# axiom_beta_interface_dummy_v0_7_eca36251.net
KiCad netlist of a schematic drawn in EAGLE
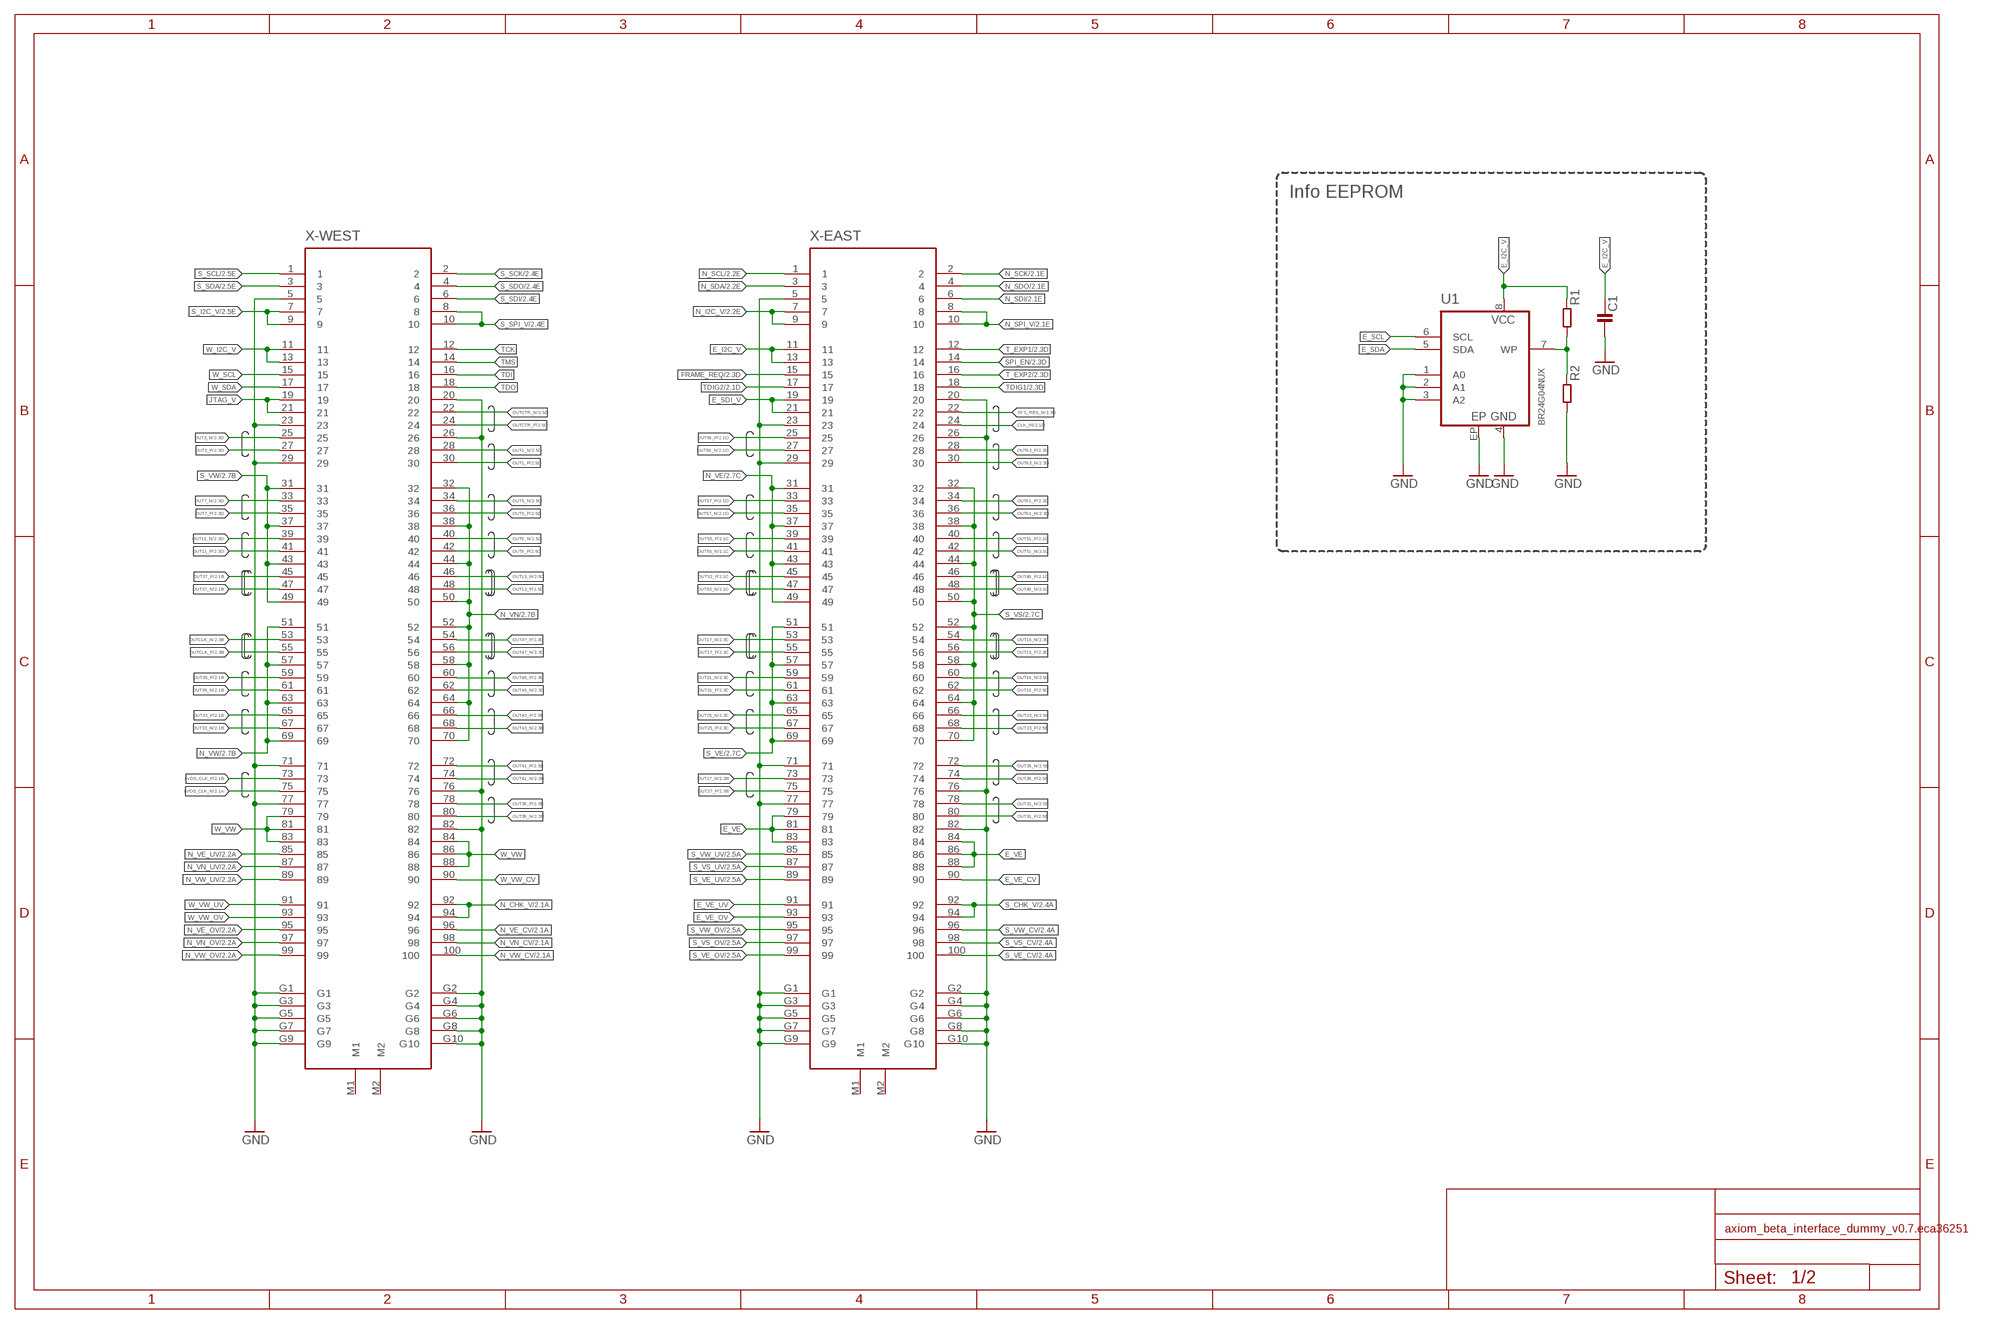
[diagram p0: schematic, sheet 1]
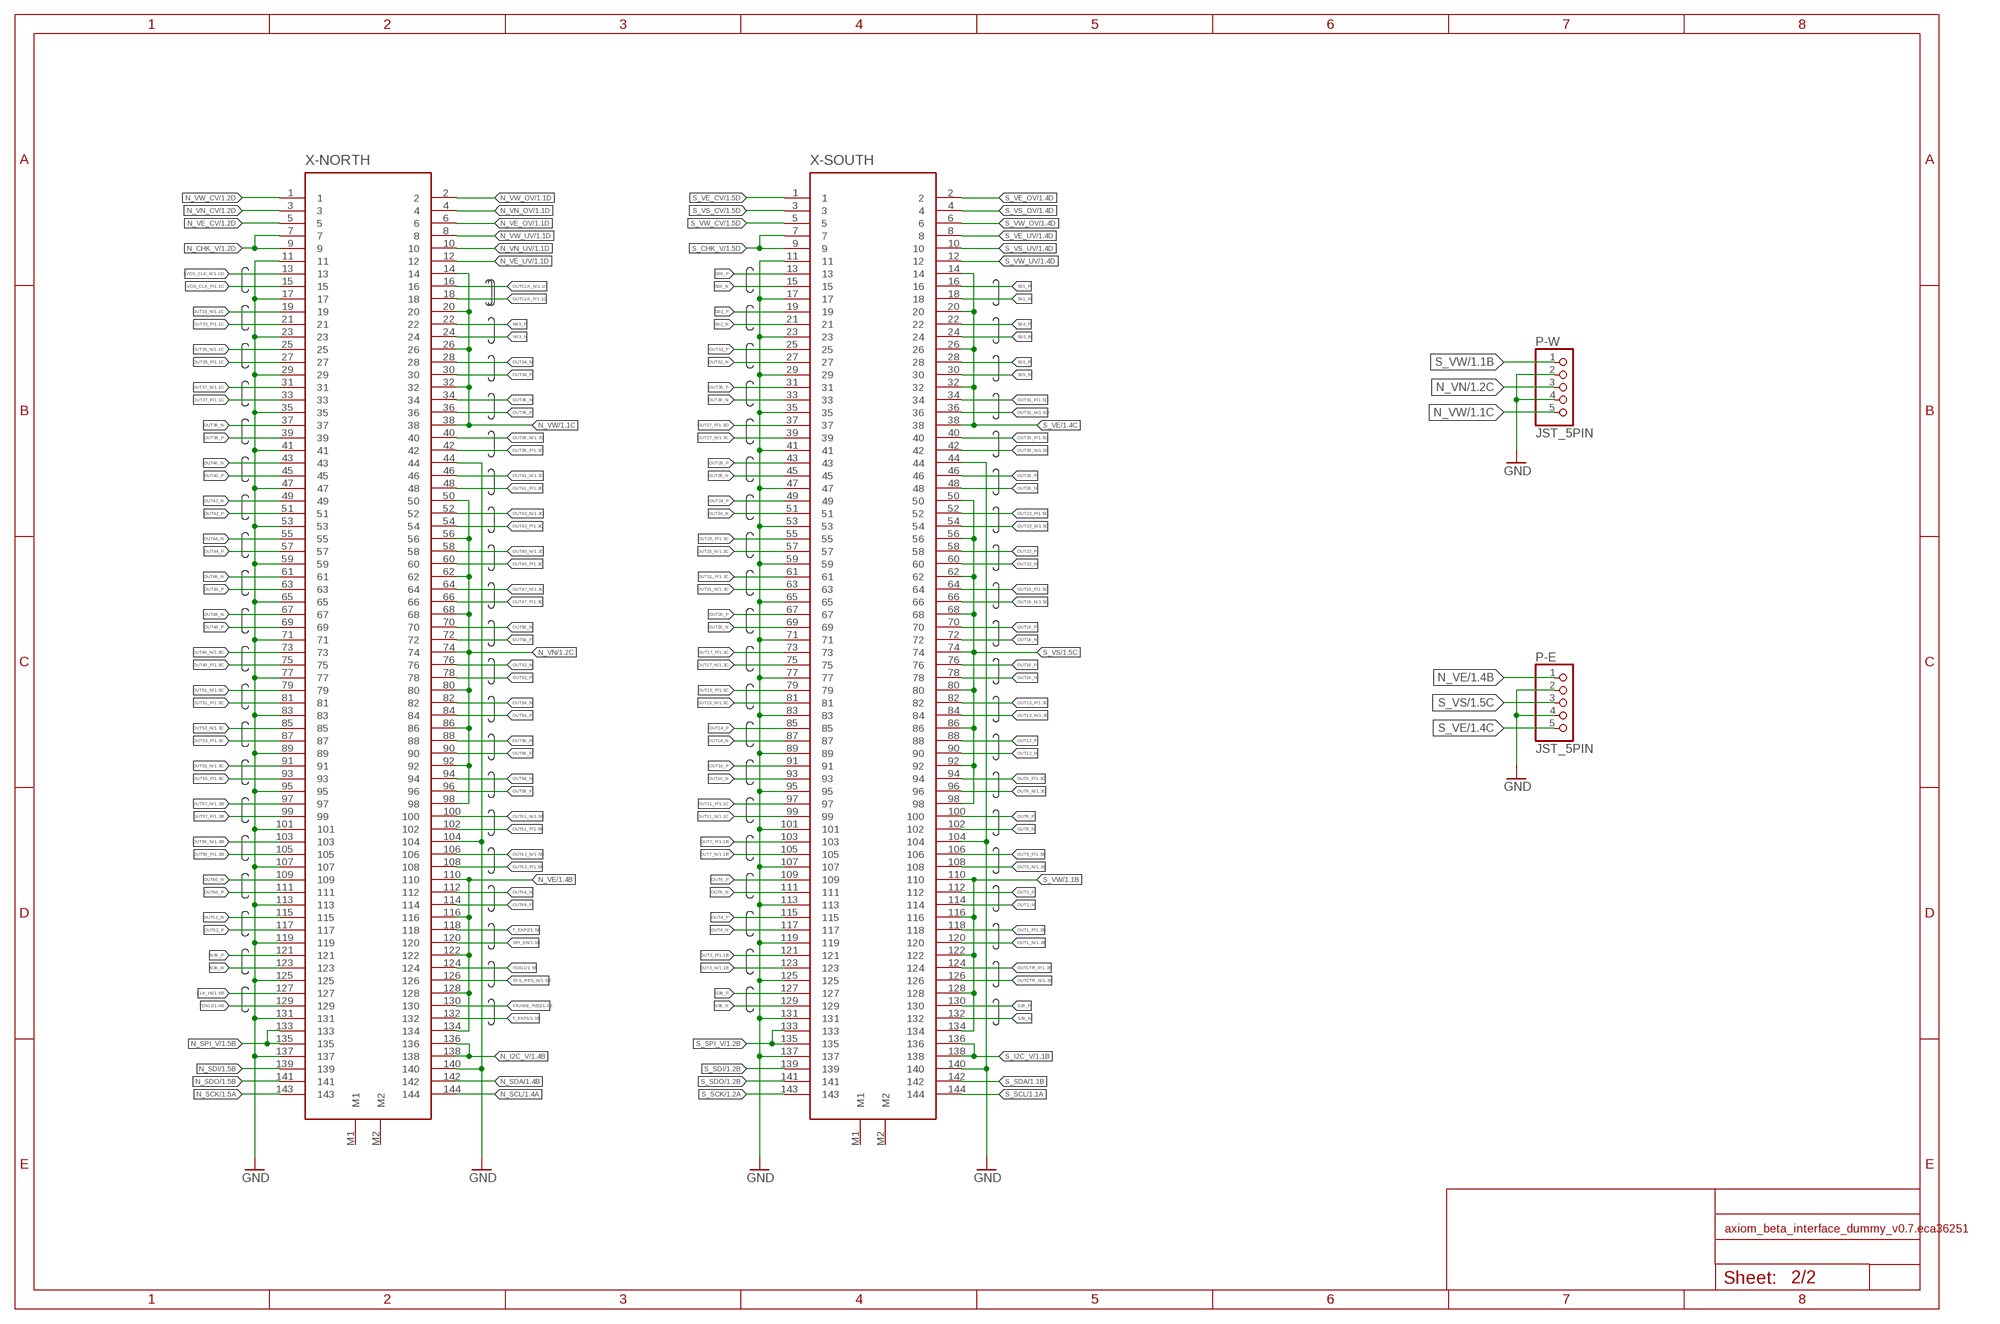
[diagram p1: schematic, sheet 2]

(export (version "E")
  (design (tool "Eeschema 10.0.6"))
  (components
    (comp (ref "P-E")
      (value "JST_5PIN")
      (footprint "eagle-import:JST-PH-5-SMT-RA")
      (libsource (lib "eagle-import") (part "JST_5PIN"))
    )
    (comp (ref "P-W")
      (value "JST_5PIN")
      (footprint "eagle-import:JST-PH-5-SMT-RA")
      (libsource (lib "eagle-import") (part "JST_5PIN"))
    )
    (comp (ref "X-NORTH")
      (value "FX10-144S")
      (footprint "eagle-import:FX10A-144S")
      (libsource (lib "eagle-import") (part "FX10-144S"))
    )
    (comp (ref "X-SOUTH")
      (value "FX10-144S")
      (footprint "eagle-import:FX10A-144S")
      (libsource (lib "eagle-import") (part "FX10-144S"))
    )
    (comp (ref "C1")
      (value "C0402-B")
      (footprint "eagle-import:0402-B")
      (libsource (lib "eagle-import") (part "C0402-B"))
    )
    (comp (ref "R1")
      (value "R0402-B")
      (footprint "eagle-import:0402-B")
      (libsource (lib "eagle-import") (part "R0402-B"))
    )
    (comp (ref "R2")
      (value "R0402-B")
      (footprint "eagle-import:0402-B")
      (libsource (lib "eagle-import") (part "R0402-B"))
    )
    (comp (ref "U1")
      (value "BR24G04NUX")
      (footprint "eagle-import:DFN200X300X100-9N")
      (libsource (lib "eagle-import") (part "BR24G04NUX"))
    )
    (comp (ref "X-EAST")
      (value "FX10-100/10P")
      (footprint "eagle-import:FX10A-100P_10")
      (libsource (lib "eagle-import") (part "FX10-100/10P"))
    )
    (comp (ref "X-WEST")
      (value "FX10-100/10P")
      (footprint "eagle-import:FX10A-100P_10")
      (libsource (lib "eagle-import") (part "FX10-100/10P"))
    )
  )
  (nets
    (net (code "1") (name "CLK_IN") (class "Default")
      (node (ref "X-EAST") (pin "24") (pinfunction "24_24") (pintype "bidirectional"))
      (node (ref "X-NORTH") (pin "127") (pinfunction "127_127") (pintype "bidirectional"))
    )
    (net (code "2") (name "E_I2C_V") (class "Default")
      (node (ref "C1") (pin "1") (pinfunction "1_1") (pintype "passive"))
      (node (ref "R1") (pin "1") (pinfunction "1_1") (pintype "passive"))
      (node (ref "U1") (pin "8") (pinfunction "VCC_8") (pintype "power_in"))
      (node (ref "X-EAST") (pin "11") (pinfunction "11_11") (pintype "bidirectional"))
      (node (ref "X-EAST") (pin "13") (pinfunction "13_13") (pintype "bidirectional"))
    )
    (net (code "3") (name "E_SCL") (class "Default")
      (node (ref "U1") (pin "6") (pinfunction "SCL_6") (pintype "input"))
    )
    (net (code "4") (name "E_SDA") (class "Default")
      (node (ref "U1") (pin "5") (pinfunction "SDA_5") (pintype "bidirectional"))
    )
    (net (code "5") (name "E_SDI_V") (class "Default")
      (node (ref "X-EAST") (pin "19") (pinfunction "19_19") (pintype "bidirectional"))
      (node (ref "X-EAST") (pin "21") (pinfunction "21_21") (pintype "bidirectional"))
    )
    (net (code "6") (name "E_VE") (class "Default")
      (node (ref "X-EAST") (pin "79") (pinfunction "79_79") (pintype "bidirectional"))
      (node (ref "X-EAST") (pin "81") (pinfunction "81_81") (pintype "bidirectional"))
      (node (ref "X-EAST") (pin "83") (pinfunction "83_83") (pintype "bidirectional"))
      (node (ref "X-EAST") (pin "84") (pinfunction "84_84") (pintype "bidirectional"))
      (node (ref "X-EAST") (pin "86") (pinfunction "86_86") (pintype "bidirectional"))
      (node (ref "X-EAST") (pin "88") (pinfunction "88_88") (pintype "bidirectional"))
    )
    (net (code "7") (name "E_VE_CV") (class "Default")
      (node (ref "X-EAST") (pin "90") (pinfunction "90_90") (pintype "bidirectional"))
    )
    (net (code "8") (name "E_VE_OV") (class "Default")
      (node (ref "X-EAST") (pin "93") (pinfunction "93_93") (pintype "bidirectional"))
    )
    (net (code "9") (name "E_VE_UV") (class "Default")
      (node (ref "X-EAST") (pin "91") (pinfunction "91_91") (pintype "bidirectional"))
    )
    (net (code "10") (name "FRAME_REQ") (class "Default")
      (node (ref "X-EAST") (pin "15") (pinfunction "15_15") (pintype "bidirectional"))
      (node (ref "X-NORTH") (pin "130") (pinfunction "130_130") (pintype "bidirectional"))
    )
    (net (code "11") (name "GND") (class "Default")
      (node (ref "C1") (pin "2") (pinfunction "2_2") (pintype "passive"))
      (node (ref "P-E") (pin "2") (pinfunction "2_2") (pintype "passive"))
      (node (ref "P-E") (pin "4") (pinfunction "4_4") (pintype "passive"))
      (node (ref "P-W") (pin "2") (pinfunction "2_2") (pintype "passive"))
      (node (ref "P-W") (pin "4") (pinfunction "4_4") (pintype "passive"))
      (node (ref "R2") (pin "2") (pinfunction "2_2") (pintype "passive"))
      (node (ref "U1") (pin "1") (pinfunction "A0_1") (pintype "input"))
      (node (ref "U1") (pin "2") (pinfunction "A1_2") (pintype "input"))
      (node (ref "U1") (pin "3") (pinfunction "A2_3") (pintype "input"))
      (node (ref "U1") (pin "4") (pinfunction "GND_4") (pintype "passive"))
      (node (ref "U1") (pin "EP") (pinfunction "EP_EP") (pintype "passive"))
      (node (ref "X-EAST") (pin "20") (pinfunction "20_20") (pintype "bidirectional"))
      (node (ref "X-EAST") (pin "23") (pinfunction "23_23") (pintype "bidirectional"))
      (node (ref "X-EAST") (pin "26") (pinfunction "26_26") (pintype "bidirectional"))
      (node (ref "X-EAST") (pin "29") (pinfunction "29_29") (pintype "bidirectional"))
      (node (ref "X-EAST") (pin "5") (pinfunction "5_5") (pintype "bidirectional"))
      (node (ref "X-EAST") (pin "71") (pinfunction "71_71") (pintype "bidirectional"))
      (node (ref "X-EAST") (pin "76") (pinfunction "76_76") (pintype "bidirectional"))
      (node (ref "X-EAST") (pin "77") (pinfunction "77_77") (pintype "bidirectional"))
      (node (ref "X-EAST") (pin "82") (pinfunction "82_82") (pintype "bidirectional"))
      (node (ref "X-EAST") (pin "G1") (pinfunction "G1_G1") (pintype "bidirectional"))
      (node (ref "X-EAST") (pin "G10") (pinfunction "G10_G10") (pintype "bidirectional"))
      (node (ref "X-EAST") (pin "G2") (pinfunction "G2_G2") (pintype "bidirectional"))
      (node (ref "X-EAST") (pin "G3") (pinfunction "G3_G3") (pintype "bidirectional"))
      (node (ref "X-EAST") (pin "G4") (pinfunction "G4_G4") (pintype "bidirectional"))
      (node (ref "X-EAST") (pin "G5") (pinfunction "G5_G5") (pintype "bidirectional"))
      (node (ref "X-EAST") (pin "G6") (pinfunction "G6_G6") (pintype "bidirectional"))
      (node (ref "X-EAST") (pin "G7") (pinfunction "G7_G7") (pintype "bidirectional"))
      (node (ref "X-EAST") (pin "G8") (pinfunction "G8_G8") (pintype "bidirectional"))
      (node (ref "X-EAST") (pin "G9") (pinfunction "G9_G9") (pintype "bidirectional"))
      (node (ref "X-NORTH") (pin "101") (pinfunction "101_101") (pintype "bidirectional"))
      (node (ref "X-NORTH") (pin "104") (pinfunction "104_104") (pintype "bidirectional"))
      (node (ref "X-NORTH") (pin "107") (pinfunction "107_107") (pintype "bidirectional"))
      (node (ref "X-NORTH") (pin "11") (pinfunction "11_11") (pintype "bidirectional"))
      (node (ref "X-NORTH") (pin "113") (pinfunction "113_113") (pintype "bidirectional"))
      (node (ref "X-NORTH") (pin "119") (pinfunction "119_119") (pintype "bidirectional"))
      (node (ref "X-NORTH") (pin "125") (pinfunction "125_125") (pintype "bidirectional"))
      (node (ref "X-NORTH") (pin "131") (pinfunction "131_131") (pintype "bidirectional"))
      (node (ref "X-NORTH") (pin "137") (pinfunction "137_137") (pintype "bidirectional"))
      (node (ref "X-NORTH") (pin "140") (pinfunction "140_140") (pintype "bidirectional"))
      (node (ref "X-NORTH") (pin "17") (pinfunction "17_17") (pintype "bidirectional"))
      (node (ref "X-NORTH") (pin "23") (pinfunction "23_23") (pintype "bidirectional"))
      (node (ref "X-NORTH") (pin "29") (pinfunction "29_29") (pintype "bidirectional"))
      (node (ref "X-NORTH") (pin "35") (pinfunction "35_35") (pintype "bidirectional"))
      (node (ref "X-NORTH") (pin "41") (pinfunction "41_41") (pintype "bidirectional"))
      (node (ref "X-NORTH") (pin "44") (pinfunction "44_44") (pintype "bidirectional"))
      (node (ref "X-NORTH") (pin "47") (pinfunction "47_47") (pintype "bidirectional"))
      (node (ref "X-NORTH") (pin "53") (pinfunction "53_53") (pintype "bidirectional"))
      (node (ref "X-NORTH") (pin "59") (pinfunction "59_59") (pintype "bidirectional"))
      (node (ref "X-NORTH") (pin "65") (pinfunction "65_65") (pintype "bidirectional"))
      (node (ref "X-NORTH") (pin "71") (pinfunction "71_71") (pintype "bidirectional"))
      (node (ref "X-NORTH") (pin "77") (pinfunction "77_77") (pintype "bidirectional"))
      (node (ref "X-NORTH") (pin "83") (pinfunction "83_83") (pintype "bidirectional"))
      (node (ref "X-NORTH") (pin "89") (pinfunction "89_89") (pintype "bidirectional"))
      (node (ref "X-NORTH") (pin "95") (pinfunction "95_95") (pintype "bidirectional"))
      (node (ref "X-SOUTH") (pin "101") (pinfunction "101_101") (pintype "bidirectional"))
      (node (ref "X-SOUTH") (pin "104") (pinfunction "104_104") (pintype "bidirectional"))
      (node (ref "X-SOUTH") (pin "107") (pinfunction "107_107") (pintype "bidirectional"))
      (node (ref "X-SOUTH") (pin "11") (pinfunction "11_11") (pintype "bidirectional"))
      (node (ref "X-SOUTH") (pin "113") (pinfunction "113_113") (pintype "bidirectional"))
      (node (ref "X-SOUTH") (pin "119") (pinfunction "119_119") (pintype "bidirectional"))
      (node (ref "X-SOUTH") (pin "125") (pinfunction "125_125") (pintype "bidirectional"))
      (node (ref "X-SOUTH") (pin "131") (pinfunction "131_131") (pintype "bidirectional"))
      (node (ref "X-SOUTH") (pin "137") (pinfunction "137_137") (pintype "bidirectional"))
      (node (ref "X-SOUTH") (pin "140") (pinfunction "140_140") (pintype "bidirectional"))
      (node (ref "X-SOUTH") (pin "17") (pinfunction "17_17") (pintype "bidirectional"))
      (node (ref "X-SOUTH") (pin "23") (pinfunction "23_23") (pintype "bidirectional"))
      (node (ref "X-SOUTH") (pin "29") (pinfunction "29_29") (pintype "bidirectional"))
      (node (ref "X-SOUTH") (pin "35") (pinfunction "35_35") (pintype "bidirectional"))
      (node (ref "X-SOUTH") (pin "41") (pinfunction "41_41") (pintype "bidirectional"))
      (node (ref "X-SOUTH") (pin "44") (pinfunction "44_44") (pintype "bidirectional"))
      (node (ref "X-SOUTH") (pin "47") (pinfunction "47_47") (pintype "bidirectional"))
      (node (ref "X-SOUTH") (pin "53") (pinfunction "53_53") (pintype "bidirectional"))
      (node (ref "X-SOUTH") (pin "59") (pinfunction "59_59") (pintype "bidirectional"))
      (node (ref "X-SOUTH") (pin "65") (pinfunction "65_65") (pintype "bidirectional"))
      (node (ref "X-SOUTH") (pin "71") (pinfunction "71_71") (pintype "bidirectional"))
      (node (ref "X-SOUTH") (pin "77") (pinfunction "77_77") (pintype "bidirectional"))
      (node (ref "X-SOUTH") (pin "83") (pinfunction "83_83") (pintype "bidirectional"))
      (node (ref "X-SOUTH") (pin "89") (pinfunction "89_89") (pintype "bidirectional"))
      (node (ref "X-SOUTH") (pin "95") (pinfunction "95_95") (pintype "bidirectional"))
      (node (ref "X-WEST") (pin "20") (pinfunction "20_20") (pintype "bidirectional"))
      (node (ref "X-WEST") (pin "23") (pinfunction "23_23") (pintype "bidirectional"))
      (node (ref "X-WEST") (pin "26") (pinfunction "26_26") (pintype "bidirectional"))
      (node (ref "X-WEST") (pin "29") (pinfunction "29_29") (pintype "bidirectional"))
      (node (ref "X-WEST") (pin "5") (pinfunction "5_5") (pintype "bidirectional"))
      (node (ref "X-WEST") (pin "71") (pinfunction "71_71") (pintype "bidirectional"))
      (node (ref "X-WEST") (pin "76") (pinfunction "76_76") (pintype "bidirectional"))
      (node (ref "X-WEST") (pin "77") (pinfunction "77_77") (pintype "bidirectional"))
      (node (ref "X-WEST") (pin "82") (pinfunction "82_82") (pintype "bidirectional"))
      (node (ref "X-WEST") (pin "G1") (pinfunction "G1_G1") (pintype "bidirectional"))
      (node (ref "X-WEST") (pin "G10") (pinfunction "G10_G10") (pintype "bidirectional"))
      (node (ref "X-WEST") (pin "G2") (pinfunction "G2_G2") (pintype "bidirectional"))
      (node (ref "X-WEST") (pin "G3") (pinfunction "G3_G3") (pintype "bidirectional"))
      (node (ref "X-WEST") (pin "G4") (pinfunction "G4_G4") (pintype "bidirectional"))
      (node (ref "X-WEST") (pin "G5") (pinfunction "G5_G5") (pintype "bidirectional"))
      (node (ref "X-WEST") (pin "G6") (pinfunction "G6_G6") (pintype "bidirectional"))
      (node (ref "X-WEST") (pin "G7") (pinfunction "G7_G7") (pintype "bidirectional"))
      (node (ref "X-WEST") (pin "G8") (pinfunction "G8_G8") (pintype "bidirectional"))
      (node (ref "X-WEST") (pin "G9") (pinfunction "G9_G9") (pintype "bidirectional"))
    )
    (net (code "12") (name "JTAG_V") (class "Default")
      (node (ref "X-WEST") (pin "19") (pinfunction "19_19") (pintype "bidirectional"))
      (node (ref "X-WEST") (pin "21") (pinfunction "21_21") (pintype "bidirectional"))
    )
    (net (code "13") (name "LVDS_CLK_N") (class "Default")
      (node (ref "X-NORTH") (pin "13") (pinfunction "13_13") (pintype "bidirectional"))
      (node (ref "X-WEST") (pin "75") (pinfunction "75_75") (pintype "bidirectional"))
    )
    (net (code "14") (name "LVDS_CLK_P") (class "Default")
      (node (ref "X-NORTH") (pin "15") (pinfunction "15_15") (pintype "bidirectional"))
      (node (ref "X-WEST") (pin "73") (pinfunction "73_73") (pintype "bidirectional"))
    )
    (net (code "15") (name "N03_N") (class "Default")
      (node (ref "X-NORTH") (pin "24") (pinfunction "24_24") (pintype "bidirectional"))
    )
    (net (code "16") (name "N03_P") (class "Default")
      (node (ref "X-NORTH") (pin "22") (pinfunction "22_22") (pintype "bidirectional"))
    )
    (net (code "17") (name "N36_N") (class "Default")
      (node (ref "X-NORTH") (pin "123") (pinfunction "123_123") (pintype "bidirectional"))
    )
    (net (code "18") (name "N36_P") (class "Default")
      (node (ref "X-NORTH") (pin "121") (pinfunction "121_121") (pintype "bidirectional"))
    )
    (net (code "19") (name "N_CHK_V") (class "Default")
      (node (ref "X-NORTH") (pin "7") (pinfunction "7_7") (pintype "bidirectional"))
      (node (ref "X-NORTH") (pin "9") (pinfunction "9_9") (pintype "bidirectional"))
      (node (ref "X-WEST") (pin "92") (pinfunction "92_92") (pintype "bidirectional"))
      (node (ref "X-WEST") (pin "94") (pinfunction "94_94") (pintype "bidirectional"))
    )
    (net (code "20") (name "N_I2C_V") (class "Default")
      (node (ref "X-EAST") (pin "7") (pinfunction "7_7") (pintype "bidirectional"))
      (node (ref "X-EAST") (pin "9") (pinfunction "9_9") (pintype "bidirectional"))
      (node (ref "X-NORTH") (pin "136") (pinfunction "136_136") (pintype "bidirectional"))
      (node (ref "X-NORTH") (pin "138") (pinfunction "138_138") (pintype "bidirectional"))
    )
    (net (code "21") (name "N_SCK") (class "Default")
      (node (ref "X-EAST") (pin "2") (pinfunction "2_2") (pintype "bidirectional"))
      (node (ref "X-NORTH") (pin "143") (pinfunction "143_143") (pintype "bidirectional"))
    )
    (net (code "22") (name "N_SCL") (class "Default")
      (node (ref "X-EAST") (pin "1") (pinfunction "1_1") (pintype "bidirectional"))
      (node (ref "X-NORTH") (pin "144") (pinfunction "144_144") (pintype "bidirectional"))
    )
    (net (code "23") (name "N_SDA") (class "Default")
      (node (ref "X-EAST") (pin "3") (pinfunction "3_3") (pintype "bidirectional"))
      (node (ref "X-NORTH") (pin "142") (pinfunction "142_142") (pintype "bidirectional"))
    )
    (net (code "24") (name "N_SDI") (class "Default")
      (node (ref "X-EAST") (pin "6") (pinfunction "6_6") (pintype "bidirectional"))
      (node (ref "X-NORTH") (pin "139") (pinfunction "139_139") (pintype "bidirectional"))
    )
    (net (code "25") (name "N_SDO") (class "Default")
      (node (ref "X-EAST") (pin "4") (pinfunction "4_4") (pintype "bidirectional"))
      (node (ref "X-NORTH") (pin "141") (pinfunction "141_141") (pintype "bidirectional"))
    )
    (net (code "26") (name "N_SPI_V") (class "Default")
      (node (ref "X-EAST") (pin "10") (pinfunction "10_10") (pintype "bidirectional"))
      (node (ref "X-EAST") (pin "8") (pinfunction "8_8") (pintype "bidirectional"))
      (node (ref "X-NORTH") (pin "133") (pinfunction "133_133") (pintype "bidirectional"))
      (node (ref "X-NORTH") (pin "135") (pinfunction "135_135") (pintype "bidirectional"))
    )
    (net (code "27") (name "N_VE") (class "Default")
      (node (ref "P-E") (pin "1") (pinfunction "1_1") (pintype "passive"))
      (node (ref "X-EAST") (pin "31") (pinfunction "31_31") (pintype "bidirectional"))
      (node (ref "X-EAST") (pin "37") (pinfunction "37_37") (pintype "bidirectional"))
      (node (ref "X-EAST") (pin "43") (pinfunction "43_43") (pintype "bidirectional"))
      (node (ref "X-EAST") (pin "49") (pinfunction "49_49") (pintype "bidirectional"))
      (node (ref "X-NORTH") (pin "110") (pinfunction "110_110") (pintype "bidirectional"))
      (node (ref "X-NORTH") (pin "116") (pinfunction "116_116") (pintype "bidirectional"))
      (node (ref "X-NORTH") (pin "122") (pinfunction "122_122") (pintype "bidirectional"))
      (node (ref "X-NORTH") (pin "128") (pinfunction "128_128") (pintype "bidirectional"))
      (node (ref "X-NORTH") (pin "134") (pinfunction "134_134") (pintype "bidirectional"))
    )
    (net (code "28") (name "N_VE_CV") (class "Default")
      (node (ref "X-NORTH") (pin "5") (pinfunction "5_5") (pintype "bidirectional"))
      (node (ref "X-WEST") (pin "96") (pinfunction "96_96") (pintype "bidirectional"))
    )
    (net (code "29") (name "N_VE_OV") (class "Default")
      (node (ref "X-NORTH") (pin "6") (pinfunction "6_6") (pintype "bidirectional"))
      (node (ref "X-WEST") (pin "95") (pinfunction "95_95") (pintype "bidirectional"))
    )
    (net (code "30") (name "N_VE_UV") (class "Default")
      (node (ref "X-NORTH") (pin "12") (pinfunction "12_12") (pintype "bidirectional"))
      (node (ref "X-WEST") (pin "85") (pinfunction "85_85") (pintype "bidirectional"))
    )
    (net (code "31") (name "N_VN") (class "Default")
      (node (ref "P-W") (pin "3") (pinfunction "3_3") (pintype "passive"))
      (node (ref "X-NORTH") (pin "50") (pinfunction "50_50") (pintype "bidirectional"))
      (node (ref "X-NORTH") (pin "56") (pinfunction "56_56") (pintype "bidirectional"))
      (node (ref "X-NORTH") (pin "62") (pinfunction "62_62") (pintype "bidirectional"))
      (node (ref "X-NORTH") (pin "68") (pinfunction "68_68") (pintype "bidirectional"))
      (node (ref "X-NORTH") (pin "74") (pinfunction "74_74") (pintype "bidirectional"))
      (node (ref "X-NORTH") (pin "80") (pinfunction "80_80") (pintype "bidirectional"))
      (node (ref "X-NORTH") (pin "86") (pinfunction "86_86") (pintype "bidirectional"))
      (node (ref "X-NORTH") (pin "92") (pinfunction "92_92") (pintype "bidirectional"))
      (node (ref "X-NORTH") (pin "98") (pinfunction "98_98") (pintype "bidirectional"))
      (node (ref "X-WEST") (pin "32") (pinfunction "32_32") (pintype "bidirectional"))
      (node (ref "X-WEST") (pin "38") (pinfunction "38_38") (pintype "bidirectional"))
      (node (ref "X-WEST") (pin "44") (pinfunction "44_44") (pintype "bidirectional"))
      (node (ref "X-WEST") (pin "50") (pinfunction "50_50") (pintype "bidirectional"))
      (node (ref "X-WEST") (pin "52") (pinfunction "52_52") (pintype "bidirectional"))
      (node (ref "X-WEST") (pin "58") (pinfunction "58_58") (pintype "bidirectional"))
      (node (ref "X-WEST") (pin "64") (pinfunction "64_64") (pintype "bidirectional"))
      (node (ref "X-WEST") (pin "70") (pinfunction "70_70") (pintype "bidirectional"))
    )
    (net (code "32") (name "N_VN_CV") (class "Default")
      (node (ref "X-NORTH") (pin "3") (pinfunction "3_3") (pintype "bidirectional"))
      (node (ref "X-WEST") (pin "98") (pinfunction "98_98") (pintype "bidirectional"))
    )
    (net (code "33") (name "N_VN_OV") (class "Default")
      (node (ref "X-NORTH") (pin "4") (pinfunction "4_4") (pintype "bidirectional"))
      (node (ref "X-WEST") (pin "97") (pinfunction "97_97") (pintype "bidirectional"))
    )
    (net (code "34") (name "N_VN_UV") (class "Default")
      (node (ref "X-NORTH") (pin "10") (pinfunction "10_10") (pintype "bidirectional"))
      (node (ref "X-WEST") (pin "87") (pinfunction "87_87") (pintype "bidirectional"))
    )
    (net (code "35") (name "N_VW") (class "Default")
      (node (ref "P-W") (pin "5") (pinfunction "5_5") (pintype "passive"))
      (node (ref "X-NORTH") (pin "14") (pinfunction "14_14") (pintype "bidirectional"))
      (node (ref "X-NORTH") (pin "20") (pinfunction "20_20") (pintype "bidirectional"))
      (node (ref "X-NORTH") (pin "26") (pinfunction "26_26") (pintype "bidirectional"))
      (node (ref "X-NORTH") (pin "32") (pinfunction "32_32") (pintype "bidirectional"))
      (node (ref "X-NORTH") (pin "38") (pinfunction "38_38") (pintype "bidirectional"))
      (node (ref "X-WEST") (pin "51") (pinfunction "51_51") (pintype "bidirectional"))
      (node (ref "X-WEST") (pin "57") (pinfunction "57_57") (pintype "bidirectional"))
      (node (ref "X-WEST") (pin "63") (pinfunction "63_63") (pintype "bidirectional"))
      (node (ref "X-WEST") (pin "69") (pinfunction "69_69") (pintype "bidirectional"))
    )
    (net (code "36") (name "N_VW_CV") (class "Default")
      (node (ref "X-NORTH") (pin "1") (pinfunction "1_1") (pintype "bidirectional"))
      (node (ref "X-WEST") (pin "100") (pinfunction "100_100") (pintype "bidirectional"))
    )
    (net (code "37") (name "N_VW_OV") (class "Default")
      (node (ref "X-NORTH") (pin "2") (pinfunction "2_2") (pintype "bidirectional"))
      (node (ref "X-WEST") (pin "99") (pinfunction "99_99") (pintype "bidirectional"))
    )
    (net (code "38") (name "N_VW_UV") (class "Default")
      (node (ref "X-NORTH") (pin "8") (pinfunction "8_8") (pintype "bidirectional"))
      (node (ref "X-WEST") (pin "89") (pinfunction "89_89") (pintype "bidirectional"))
    )
    (net (code "39") (name "Net-(U1-WP)") (class "Default")
      (node (ref "R1") (pin "2") (pinfunction "2_2") (pintype "passive"))
      (node (ref "R2") (pin "1") (pinfunction "1_1") (pintype "passive"))
      (node (ref "U1") (pin "7") (pinfunction "WP_7") (pintype "input"))
    )
    (net (code "40") (name "OUT1_N") (class "Default")
      (node (ref "X-SOUTH") (pin "120") (pinfunction "120_120") (pintype "bidirectional"))
      (node (ref "X-WEST") (pin "28") (pinfunction "28_28") (pintype "bidirectional"))
    )
    (net (code "41") (name "OUT1_P") (class "Default")
      (node (ref "X-SOUTH") (pin "118") (pinfunction "118_118") (pintype "bidirectional"))
      (node (ref "X-WEST") (pin "30") (pinfunction "30_30") (pintype "bidirectional"))
    )
    (net (code "42") (name "OUT2_N") (class "Default")
      (node (ref "X-SOUTH") (pin "114") (pinfunction "114_114") (pintype "bidirectional"))
    )
    (net (code "43") (name "OUT2_P") (class "Default")
      (node (ref "X-SOUTH") (pin "112") (pinfunction "112_112") (pintype "bidirectional"))
    )
    (net (code "44") (name "OUT3_N") (class "Default")
      (node (ref "X-SOUTH") (pin "123") (pinfunction "123_123") (pintype "bidirectional"))
      (node (ref "X-WEST") (pin "25") (pinfunction "25_25") (pintype "bidirectional"))
    )
    (net (code "45") (name "OUT3_P") (class "Default")
      (node (ref "X-SOUTH") (pin "121") (pinfunction "121_121") (pintype "bidirectional"))
      (node (ref "X-WEST") (pin "27") (pinfunction "27_27") (pintype "bidirectional"))
    )
    (net (code "46") (name "OUT4_N") (class "Default")
      (node (ref "X-SOUTH") (pin "117") (pinfunction "117_117") (pintype "bidirectional"))
    )
    (net (code "47") (name "OUT4_P") (class "Default")
      (node (ref "X-SOUTH") (pin "115") (pinfunction "115_115") (pintype "bidirectional"))
    )
    (net (code "48") (name "OUT5_N") (class "Default")
      (node (ref "X-SOUTH") (pin "108") (pinfunction "108_108") (pintype "bidirectional"))
      (node (ref "X-WEST") (pin "34") (pinfunction "34_34") (pintype "bidirectional"))
    )
    (net (code "49") (name "OUT5_P") (class "Default")
      (node (ref "X-SOUTH") (pin "106") (pinfunction "106_106") (pintype "bidirectional"))
      (node (ref "X-WEST") (pin "36") (pinfunction "36_36") (pintype "bidirectional"))
    )
    (net (code "50") (name "OUT6_N") (class "Default")
      (node (ref "X-SOUTH") (pin "111") (pinfunction "111_111") (pintype "bidirectional"))
    )
    (net (code "51") (name "OUT6_P") (class "Default")
      (node (ref "X-SOUTH") (pin "109") (pinfunction "109_109") (pintype "bidirectional"))
    )
    (net (code "52") (name "OUT7_N") (class "Default")
      (node (ref "X-SOUTH") (pin "105") (pinfunction "105_105") (pintype "bidirectional"))
      (node (ref "X-WEST") (pin "33") (pinfunction "33_33") (pintype "bidirectional"))
    )
    (net (code "53") (name "OUT7_P") (class "Default")
      (node (ref "X-SOUTH") (pin "103") (pinfunction "103_103") (pintype "bidirectional"))
      (node (ref "X-WEST") (pin "35") (pinfunction "35_35") (pintype "bidirectional"))
    )
    (net (code "54") (name "OUT8_N") (class "Default")
      (node (ref "X-SOUTH") (pin "102") (pinfunction "102_102") (pintype "bidirectional"))
    )
    (net (code "55") (name "OUT8_P") (class "Default")
      (node (ref "X-SOUTH") (pin "100") (pinfunction "100_100") (pintype "bidirectional"))
    )
    (net (code "56") (name "OUT9_N") (class "Default")
      (node (ref "X-SOUTH") (pin "96") (pinfunction "96_96") (pintype "bidirectional"))
      (node (ref "X-WEST") (pin "40") (pinfunction "40_40") (pintype "bidirectional"))
    )
    (net (code "57") (name "OUT9_P") (class "Default")
      (node (ref "X-SOUTH") (pin "94") (pinfunction "94_94") (pintype "bidirectional"))
      (node (ref "X-WEST") (pin "42") (pinfunction "42_42") (pintype "bidirectional"))
    )
    (net (code "58") (name "OUT10_N") (class "Default")
      (node (ref "X-SOUTH") (pin "93") (pinfunction "93_93") (pintype "bidirectional"))
    )
    (net (code "59") (name "OUT10_P") (class "Default")
      (node (ref "X-SOUTH") (pin "91") (pinfunction "91_91") (pintype "bidirectional"))
    )
    (net (code "60") (name "OUT11_N") (class "Default")
      (node (ref "X-SOUTH") (pin "99") (pinfunction "99_99") (pintype "bidirectional"))
      (node (ref "X-WEST") (pin "39") (pinfunction "39_39") (pintype "bidirectional"))
    )
    (net (code "61") (name "OUT11_P") (class "Default")
      (node (ref "X-SOUTH") (pin "97") (pinfunction "97_97") (pintype "bidirectional"))
      (node (ref "X-WEST") (pin "41") (pinfunction "41_41") (pintype "bidirectional"))
    )
    (net (code "62") (name "OUT12_N") (class "Default")
      (node (ref "X-SOUTH") (pin "90") (pinfunction "90_90") (pintype "bidirectional"))
    )
    (net (code "63") (name "OUT12_P") (class "Default")
      (node (ref "X-SOUTH") (pin "88") (pinfunction "88_88") (pintype "bidirectional"))
    )
    (net (code "64") (name "OUT13_N") (class "Default")
      (node (ref "X-SOUTH") (pin "84") (pinfunction "84_84") (pintype "bidirectional"))
      (node (ref "X-WEST") (pin "46") (pinfunction "46_46") (pintype "bidirectional"))
    )
    (net (code "65") (name "OUT13_P") (class "Default")
      (node (ref "X-SOUTH") (pin "82") (pinfunction "82_82") (pintype "bidirectional"))
      (node (ref "X-WEST") (pin "48") (pinfunction "48_48") (pintype "bidirectional"))
    )
    (net (code "66") (name "OUT14_N") (class "Default")
      (node (ref "X-SOUTH") (pin "87") (pinfunction "87_87") (pintype "bidirectional"))
    )
    (net (code "67") (name "OUT14_P") (class "Default")
      (node (ref "X-SOUTH") (pin "85") (pinfunction "85_85") (pintype "bidirectional"))
    )
    (net (code "68") (name "OUT15_N") (class "Default")
      (node (ref "X-EAST") (pin "54") (pinfunction "54_54") (pintype "bidirectional"))
      (node (ref "X-SOUTH") (pin "81") (pinfunction "81_81") (pintype "bidirectional"))
    )
    (net (code "69") (name "OUT15_P") (class "Default")
      (node (ref "X-EAST") (pin "56") (pinfunction "56_56") (pintype "bidirectional"))
      (node (ref "X-SOUTH") (pin "79") (pinfunction "79_79") (pintype "bidirectional"))
    )
    (net (code "70") (name "OUT16_N") (class "Default")
      (node (ref "X-SOUTH") (pin "78") (pinfunction "78_78") (pintype "bidirectional"))
    )
    (net (code "71") (name "OUT16_P") (class "Default")
      (node (ref "X-SOUTH") (pin "76") (pinfunction "76_76") (pintype "bidirectional"))
    )
    (net (code "72") (name "OUT17_N") (class "Default")
      (node (ref "X-EAST") (pin "53") (pinfunction "53_53") (pintype "bidirectional"))
      (node (ref "X-SOUTH") (pin "75") (pinfunction "75_75") (pintype "bidirectional"))
    )
    (net (code "73") (name "OUT17_P") (class "Default")
      (node (ref "X-EAST") (pin "55") (pinfunction "55_55") (pintype "bidirectional"))
      (node (ref "X-SOUTH") (pin "73") (pinfunction "73_73") (pintype "bidirectional"))
    )
    (net (code "74") (name "OUT18_N") (class "Default")
      (node (ref "X-SOUTH") (pin "72") (pinfunction "72_72") (pintype "bidirectional"))
    )
    (net (code "75") (name "OUT18_P") (class "Default")
      (node (ref "X-SOUTH") (pin "70") (pinfunction "70_70") (pintype "bidirectional"))
    )
    (net (code "76") (name "OUT19_N") (class "Default")
      (node (ref "X-EAST") (pin "60") (pinfunction "60_60") (pintype "bidirectional"))
      (node (ref "X-SOUTH") (pin "66") (pinfunction "66_66") (pintype "bidirectional"))
    )
    (net (code "77") (name "OUT19_P") (class "Default")
      (node (ref "X-EAST") (pin "62") (pinfunction "62_62") (pintype "bidirectional"))
      (node (ref "X-SOUTH") (pin "64") (pinfunction "64_64") (pintype "bidirectional"))
    )
    (net (code "78") (name "OUT20_N") (class "Default")
      (node (ref "X-SOUTH") (pin "69") (pinfunction "69_69") (pintype "bidirectional"))
    )
    (net (code "79") (name "OUT20_P") (class "Default")
      (node (ref "X-SOUTH") (pin "67") (pinfunction "67_67") (pintype "bidirectional"))
    )
    (net (code "80") (name "OUT21_N") (class "Default")
      (node (ref "X-EAST") (pin "59") (pinfunction "59_59") (pintype "bidirectional"))
      (node (ref "X-SOUTH") (pin "63") (pinfunction "63_63") (pintype "bidirectional"))
    )
    (net (code "81") (name "OUT21_P") (class "Default")
      (node (ref "X-EAST") (pin "61") (pinfunction "61_61") (pintype "bidirectional"))
      (node (ref "X-SOUTH") (pin "61") (pinfunction "61_61") (pintype "bidirectional"))
    )
    (net (code "82") (name "OUT22_N") (class "Default")
      (node (ref "X-SOUTH") (pin "60") (pinfunction "60_60") (pintype "bidirectional"))
    )
    (net (code "83") (name "OUT22_P") (class "Default")
      (node (ref "X-SOUTH") (pin "58") (pinfunction "58_58") (pintype "bidirectional"))
    )
    (net (code "84") (name "OUT23_N") (class "Default")
      (node (ref "X-EAST") (pin "66") (pinfunction "66_66") (pintype "bidirectional"))
      (node (ref "X-SOUTH") (pin "54") (pinfunction "54_54") (pintype "bidirectional"))
    )
    (net (code "85") (name "OUT23_P") (class "Default")
      (node (ref "X-EAST") (pin "68") (pinfunction "68_68") (pintype "bidirectional"))
      (node (ref "X-SOUTH") (pin "52") (pinfunction "52_52") (pintype "bidirectional"))
    )
    (net (code "86") (name "OUT24_N") (class "Default")
      (node (ref "X-SOUTH") (pin "51") (pinfunction "51_51") (pintype "bidirectional"))
    )
    (net (code "87") (name "OUT24_P") (class "Default")
      (node (ref "X-SOUTH") (pin "49") (pinfunction "49_49") (pintype "bidirectional"))
    )
    (net (code "88") (name "OUT25_N") (class "Default")
      (node (ref "X-EAST") (pin "65") (pinfunction "65_65") (pintype "bidirectional"))
      (node (ref "X-SOUTH") (pin "57") (pinfunction "57_57") (pintype "bidirectional"))
    )
    (net (code "89") (name "OUT25_P") (class "Default")
      (node (ref "X-EAST") (pin "67") (pinfunction "67_67") (pintype "bidirectional"))
      (node (ref "X-SOUTH") (pin "55") (pinfunction "55_55") (pintype "bidirectional"))
    )
    (net (code "90") (name "OUT26_N") (class "Default")
      (node (ref "X-SOUTH") (pin "48") (pinfunction "48_48") (pintype "bidirectional"))
    )
    (net (code "91") (name "OUT26_P") (class "Default")
      (node (ref "X-SOUTH") (pin "46") (pinfunction "46_46") (pintype "bidirectional"))
    )
    (net (code "92") (name "OUT27_N") (class "Default")
      (node (ref "X-EAST") (pin "73") (pinfunction "73_73") (pintype "bidirectional"))
      (node (ref "X-SOUTH") (pin "39") (pinfunction "39_39") (pintype "bidirectional"))
    )
    (net (code "93") (name "OUT27_P") (class "Default")
      (node (ref "X-EAST") (pin "75") (pinfunction "75_75") (pintype "bidirectional"))
      (node (ref "X-SOUTH") (pin "37") (pinfunction "37_37") (pintype "bidirectional"))
    )
    (net (code "94") (name "OUT28_N") (class "Default")
      (node (ref "X-SOUTH") (pin "45") (pinfunction "45_45") (pintype "bidirectional"))
    )
    (net (code "95") (name "OUT28_P") (class "Default")
      (node (ref "X-SOUTH") (pin "43") (pinfunction "43_43") (pintype "bidirectional"))
    )
    (net (code "96") (name "OUT29_N") (class "Default")
      (node (ref "X-EAST") (pin "72") (pinfunction "72_72") (pintype "bidirectional"))
      (node (ref "X-SOUTH") (pin "42") (pinfunction "42_42") (pintype "bidirectional"))
    )
    (net (code "97") (name "OUT29_P") (class "Default")
      (node (ref "X-EAST") (pin "74") (pinfunction "74_74") (pintype "bidirectional"))
      (node (ref "X-SOUTH") (pin "40") (pinfunction "40_40") (pintype "bidirectional"))
    )
    (net (code "98") (name "OUT30_N") (class "Default")
      (node (ref "X-SOUTH") (pin "33") (pinfunction "33_33") (pintype "bidirectional"))
    )
    (net (code "99") (name "OUT30_P") (class "Default")
      (node (ref "X-SOUTH") (pin "31") (pinfunction "31_31") (pintype "bidirectional"))
    )
    (net (code "100") (name "OUT31_N") (class "Default")
      (node (ref "X-EAST") (pin "78") (pinfunction "78_78") (pintype "bidirectional"))
      (node (ref "X-SOUTH") (pin "36") (pinfunction "36_36") (pintype "bidirectional"))
    )
    (net (code "101") (name "OUT31_P") (class "Default")
      (node (ref "X-EAST") (pin "80") (pinfunction "80_80") (pintype "bidirectional"))
      (node (ref "X-SOUTH") (pin "34") (pinfunction "34_34") (pintype "bidirectional"))
    )
    (net (code "102") (name "OUT32_N") (class "Default")
      (node (ref "X-SOUTH") (pin "27") (pinfunction "27_27") (pintype "bidirectional"))
    )
    (net (code "103") (name "OUT32_P") (class "Default")
      (node (ref "X-SOUTH") (pin "25") (pinfunction "25_25") (pintype "bidirectional"))
    )
    (net (code "104") (name "OUT33_N") (class "Default")
      (node (ref "X-NORTH") (pin "19") (pinfunction "19_19") (pintype "bidirectional"))
      (node (ref "X-WEST") (pin "67") (pinfunction "67_67") (pintype "bidirectional"))
    )
    (net (code "105") (name "OUT33_P") (class "Default")
      (node (ref "X-NORTH") (pin "21") (pinfunction "21_21") (pintype "bidirectional"))
      (node (ref "X-WEST") (pin "65") (pinfunction "65_65") (pintype "bidirectional"))
    )
    (net (code "106") (name "OUT34_N") (class "Default")
      (node (ref "X-NORTH") (pin "28") (pinfunction "28_28") (pintype "bidirectional"))
    )
    (net (code "107") (name "OUT34_P") (class "Default")
      (node (ref "X-NORTH") (pin "30") (pinfunction "30_30") (pintype "bidirectional"))
    )
    (net (code "108") (name "OUT35_N") (class "Default")
      (node (ref "X-NORTH") (pin "25") (pinfunction "25_25") (pintype "bidirectional"))
      (node (ref "X-WEST") (pin "61") (pinfunction "61_61") (pintype "bidirectional"))
    )
    (net (code "109") (name "OUT35_P") (class "Default")
      (node (ref "X-NORTH") (pin "27") (pinfunction "27_27") (pintype "bidirectional"))
      (node (ref "X-WEST") (pin "59") (pinfunction "59_59") (pintype "bidirectional"))
    )
    (net (code "110") (name "OUT36_N") (class "Default")
      (node (ref "X-NORTH") (pin "34") (pinfunction "34_34") (pintype "bidirectional"))
    )
    (net (code "111") (name "OUT36_P") (class "Default")
      (node (ref "X-NORTH") (pin "36") (pinfunction "36_36") (pintype "bidirectional"))
    )
    (net (code "112") (name "OUT37_N") (class "Default")
      (node (ref "X-NORTH") (pin "31") (pinfunction "31_31") (pintype "bidirectional"))
      (node (ref "X-WEST") (pin "47") (pinfunction "47_47") (pintype "bidirectional"))
    )
    (net (code "113") (name "OUT37_P") (class "Default")
      (node (ref "X-NORTH") (pin "33") (pinfunction "33_33") (pintype "bidirectional"))
      (node (ref "X-WEST") (pin "45") (pinfunction "45_45") (pintype "bidirectional"))
    )
    (net (code "114") (name "OUT38_N") (class "Default")
      (node (ref "X-NORTH") (pin "37") (pinfunction "37_37") (pintype "bidirectional"))
    )
    (net (code "115") (name "OUT38_P") (class "Default")
      (node (ref "X-NORTH") (pin "39") (pinfunction "39_39") (pintype "bidirectional"))
    )
    (net (code "116") (name "OUT39_N") (class "Default")
      (node (ref "X-NORTH") (pin "40") (pinfunction "40_40") (pintype "bidirectional"))
      (node (ref "X-WEST") (pin "80") (pinfunction "80_80") (pintype "bidirectional"))
    )
    (net (code "117") (name "OUT39_P") (class "Default")
      (node (ref "X-NORTH") (pin "42") (pinfunction "42_42") (pintype "bidirectional"))
      (node (ref "X-WEST") (pin "78") (pinfunction "78_78") (pintype "bidirectional"))
    )
    (net (code "118") (name "OUT40_N") (class "Default")
      (node (ref "X-NORTH") (pin "43") (pinfunction "43_43") (pintype "bidirectional"))
    )
    (net (code "119") (name "OUT40_P") (class "Default")
      (node (ref "X-NORTH") (pin "45") (pinfunction "45_45") (pintype "bidirectional"))
    )
    (net (code "120") (name "OUT41_N") (class "Default")
      (node (ref "X-NORTH") (pin "46") (pinfunction "46_46") (pintype "bidirectional"))
      (node (ref "X-WEST") (pin "74") (pinfunction "74_74") (pintype "bidirectional"))
    )
    (net (code "121") (name "OUT41_P") (class "Default")
      (node (ref "X-NORTH") (pin "48") (pinfunction "48_48") (pintype "bidirectional"))
      (node (ref "X-WEST") (pin "72") (pinfunction "72_72") (pintype "bidirectional"))
    )
    (net (code "122") (name "OUT42_N") (class "Default")
      (node (ref "X-NORTH") (pin "49") (pinfunction "49_49") (pintype "bidirectional"))
    )
    (net (code "123") (name "OUT42_P") (class "Default")
      (node (ref "X-NORTH") (pin "51") (pinfunction "51_51") (pintype "bidirectional"))
    )
    (net (code "124") (name "OUT43_N") (class "Default")
      (node (ref "X-NORTH") (pin "52") (pinfunction "52_52") (pintype "bidirectional"))
      (node (ref "X-WEST") (pin "68") (pinfunction "68_68") (pintype "bidirectional"))
    )
    (net (code "125") (name "OUT43_P") (class "Default")
      (node (ref "X-NORTH") (pin "54") (pinfunction "54_54") (pintype "bidirectional"))
      (node (ref "X-WEST") (pin "66") (pinfunction "66_66") (pintype "bidirectional"))
    )
    (net (code "126") (name "OUT44_N") (class "Default")
      (node (ref "X-NORTH") (pin "55") (pinfunction "55_55") (pintype "bidirectional"))
    )
    (net (code "127") (name "OUT44_P") (class "Default")
      (node (ref "X-NORTH") (pin "57") (pinfunction "57_57") (pintype "bidirectional"))
    )
    (net (code "128") (name "OUT45_N") (class "Default")
      (node (ref "X-NORTH") (pin "58") (pinfunction "58_58") (pintype "bidirectional"))
      (node (ref "X-WEST") (pin "62") (pinfunction "62_62") (pintype "bidirectional"))
    )
    (net (code "129") (name "OUT45_P") (class "Default")
      (node (ref "X-NORTH") (pin "60") (pinfunction "60_60") (pintype "bidirectional"))
      (node (ref "X-WEST") (pin "60") (pinfunction "60_60") (pintype "bidirectional"))
    )
    (net (code "130") (name "OUT46_N") (class "Default")
      (node (ref "X-NORTH") (pin "61") (pinfunction "61_61") (pintype "bidirectional"))
    )
    (net (code "131") (name "OUT46_P") (class "Default")
      (node (ref "X-NORTH") (pin "63") (pinfunction "63_63") (pintype "bidirectional"))
    )
    (net (code "132") (name "OUT47_N") (class "Default")
      (node (ref "X-NORTH") (pin "64") (pinfunction "64_64") (pintype "bidirectional"))
      (node (ref "X-WEST") (pin "56") (pinfunction "56_56") (pintype "bidirectional"))
    )
    (net (code "133") (name "OUT47_P") (class "Default")
      (node (ref "X-NORTH") (pin "66") (pinfunction "66_66") (pintype "bidirectional"))
      (node (ref "X-WEST") (pin "54") (pinfunction "54_54") (pintype "bidirectional"))
    )
    (net (code "134") (name "OUT48_N") (class "Default")
      (node (ref "X-NORTH") (pin "67") (pinfunction "67_67") (pintype "bidirectional"))
    )
    (net (code "135") (name "OUT48_P") (class "Default")
      (node (ref "X-NORTH") (pin "69") (pinfunction "69_69") (pintype "bidirectional"))
    )
    (net (code "136") (name "OUT49_N") (class "Default")
      (node (ref "X-EAST") (pin "48") (pinfunction "48_48") (pintype "bidirectional"))
      (node (ref "X-NORTH") (pin "73") (pinfunction "73_73") (pintype "bidirectional"))
    )
    (net (code "137") (name "OUT49_P") (class "Default")
      (node (ref "X-EAST") (pin "46") (pinfunction "46_46") (pintype "bidirectional"))
      (node (ref "X-NORTH") (pin "75") (pinfunction "75_75") (pintype "bidirectional"))
    )
    (net (code "138") (name "OUT50_N") (class "Default")
      (node (ref "X-NORTH") (pin "70") (pinfunction "70_70") (pintype "bidirectional"))
    )
    (net (code "139") (name "OUT50_P") (class "Default")
      (node (ref "X-NORTH") (pin "72") (pinfunction "72_72") (pintype "bidirectional"))
    )
    (net (code "140") (name "OUT51_N") (class "Default")
      (node (ref "X-EAST") (pin "42") (pinfunction "42_42") (pintype "bidirectional"))
      (node (ref "X-NORTH") (pin "79") (pinfunction "79_79") (pintype "bidirectional"))
    )
    (net (code "141") (name "OUT51_P") (class "Default")
      (node (ref "X-EAST") (pin "40") (pinfunction "40_40") (pintype "bidirectional"))
      (node (ref "X-NORTH") (pin "81") (pinfunction "81_81") (pintype "bidirectional"))
    )
    (net (code "142") (name "OUT52_N") (class "Default")
      (node (ref "X-NORTH") (pin "76") (pinfunction "76_76") (pintype "bidirectional"))
    )
    (net (code "143") (name "OUT52_P") (class "Default")
      (node (ref "X-NORTH") (pin "78") (pinfunction "78_78") (pintype "bidirectional"))
    )
    (net (code "144") (name "OUT53_N") (class "Default")
      (node (ref "X-EAST") (pin "47") (pinfunction "47_47") (pintype "bidirectional"))
      (node (ref "X-NORTH") (pin "85") (pinfunction "85_85") (pintype "bidirectional"))
    )
    (net (code "145") (name "OUT53_P") (class "Default")
      (node (ref "X-EAST") (pin "45") (pinfunction "45_45") (pintype "bidirectional"))
      (node (ref "X-NORTH") (pin "87") (pinfunction "87_87") (pintype "bidirectional"))
    )
    (net (code "146") (name "OUT54_N") (class "Default")
      (node (ref "X-NORTH") (pin "82") (pinfunction "82_82") (pintype "bidirectional"))
    )
    (net (code "147") (name "OUT54_P") (class "Default")
      (node (ref "X-NORTH") (pin "84") (pinfunction "84_84") (pintype "bidirectional"))
    )
    (net (code "148") (name "OUT55_N") (class "Default")
      (node (ref "X-EAST") (pin "41") (pinfunction "41_41") (pintype "bidirectional"))
      (node (ref "X-NORTH") (pin "91") (pinfunction "91_91") (pintype "bidirectional"))
    )
    (net (code "149") (name "OUT55_P") (class "Default")
      (node (ref "X-EAST") (pin "39") (pinfunction "39_39") (pintype "bidirectional"))
      (node (ref "X-NORTH") (pin "93") (pinfunction "93_93") (pintype "bidirectional"))
    )
    (net (code "150") (name "OUT56_N") (class "Default")
      (node (ref "X-NORTH") (pin "88") (pinfunction "88_88") (pintype "bidirectional"))
    )
    (net (code "151") (name "OUT56_P") (class "Default")
      (node (ref "X-NORTH") (pin "90") (pinfunction "90_90") (pintype "bidirectional"))
    )
    (net (code "152") (name "OUT57_N") (class "Default")
      (node (ref "X-EAST") (pin "35") (pinfunction "35_35") (pintype "bidirectional"))
      (node (ref "X-NORTH") (pin "97") (pinfunction "97_97") (pintype "bidirectional"))
    )
    (net (code "153") (name "OUT57_P") (class "Default")
      (node (ref "X-EAST") (pin "33") (pinfunction "33_33") (pintype "bidirectional"))
      (node (ref "X-NORTH") (pin "99") (pinfunction "99_99") (pintype "bidirectional"))
    )
    (net (code "154") (name "OUT58_N") (class "Default")
      (node (ref "X-NORTH") (pin "94") (pinfunction "94_94") (pintype "bidirectional"))
    )
    (net (code "155") (name "OUT58_P") (class "Default")
      (node (ref "X-NORTH") (pin "96") (pinfunction "96_96") (pintype "bidirectional"))
    )
    (net (code "156") (name "OUT59_N") (class "Default")
      (node (ref "X-EAST") (pin "27") (pinfunction "27_27") (pintype "bidirectional"))
      (node (ref "X-NORTH") (pin "103") (pinfunction "103_103") (pintype "bidirectional"))
    )
    (net (code "157") (name "OUT59_P") (class "Default")
      (node (ref "X-EAST") (pin "25") (pinfunction "25_25") (pintype "bidirectional"))
      (node (ref "X-NORTH") (pin "105") (pinfunction "105_105") (pintype "bidirectional"))
    )
    (net (code "158") (name "OUT60_N") (class "Default")
      (node (ref "X-NORTH") (pin "109") (pinfunction "109_109") (pintype "bidirectional"))
    )
    (net (code "159") (name "OUT60_P") (class "Default")
      (node (ref "X-NORTH") (pin "111") (pinfunction "111_111") (pintype "bidirectional"))
    )
    (net (code "160") (name "OUT61_N") (class "Default")
      (node (ref "X-EAST") (pin "36") (pinfunction "36_36") (pintype "bidirectional"))
      (node (ref "X-NORTH") (pin "100") (pinfunction "100_100") (pintype "bidirectional"))
    )
    (net (code "161") (name "OUT61_P") (class "Default")
      (node (ref "X-EAST") (pin "34") (pinfunction "34_34") (pintype "bidirectional"))
      (node (ref "X-NORTH") (pin "102") (pinfunction "102_102") (pintype "bidirectional"))
    )
    (net (code "162") (name "OUT62_N") (class "Default")
      (node (ref "X-NORTH") (pin "115") (pinfunction "115_115") (pintype "bidirectional"))
    )
    (net (code "163") (name "OUT62_P") (class "Default")
      (node (ref "X-NORTH") (pin "117") (pinfunction "117_117") (pintype "bidirectional"))
    )
    (net (code "164") (name "OUT63_N") (class "Default")
      (node (ref "X-EAST") (pin "30") (pinfunction "30_30") (pintype "bidirectional"))
      (node (ref "X-NORTH") (pin "106") (pinfunction "106_106") (pintype "bidirectional"))
    )
    (net (code "165") (name "OUT63_P") (class "Default")
      (node (ref "X-EAST") (pin "28") (pinfunction "28_28") (pintype "bidirectional"))
      (node (ref "X-NORTH") (pin "108") (pinfunction "108_108") (pintype "bidirectional"))
    )
    (net (code "166") (name "OUT64_N") (class "Default")
      (node (ref "X-NORTH") (pin "112") (pinfunction "112_112") (pintype "bidirectional"))
    )
    (net (code "167") (name "OUT64_P") (class "Default")
      (node (ref "X-NORTH") (pin "114") (pinfunction "114_114") (pintype "bidirectional"))
    )
    (net (code "168") (name "OUTCLK_N") (class "Default")
      (node (ref "X-NORTH") (pin "16") (pinfunction "16_16") (pintype "bidirectional"))
      (node (ref "X-WEST") (pin "53") (pinfunction "53_53") (pintype "bidirectional"))
    )
    (net (code "169") (name "OUTCLK_P") (class "Default")
      (node (ref "X-NORTH") (pin "18") (pinfunction "18_18") (pintype "bidirectional"))
      (node (ref "X-WEST") (pin "55") (pinfunction "55_55") (pintype "bidirectional"))
    )
    (net (code "170") (name "OUTCTR_N") (class "Default")
      (node (ref "X-SOUTH") (pin "126") (pinfunction "126_126") (pintype "bidirectional"))
      (node (ref "X-WEST") (pin "22") (pinfunction "22_22") (pintype "bidirectional"))
    )
    (net (code "171") (name "OUTCTR_P") (class "Default")
      (node (ref "X-SOUTH") (pin "124") (pinfunction "124_124") (pintype "bidirectional"))
      (node (ref "X-WEST") (pin "24") (pinfunction "24_24") (pintype "bidirectional"))
    )
    (net (code "172") (name "S00_N") (class "Default")
      (node (ref "X-SOUTH") (pin "15") (pinfunction "15_15") (pintype "bidirectional"))
    )
    (net (code "173") (name "S00_P") (class "Default")
      (node (ref "X-SOUTH") (pin "13") (pinfunction "13_13") (pintype "bidirectional"))
    )
    (net (code "174") (name "S01_N") (class "Default")
      (node (ref "X-SOUTH") (pin "18") (pinfunction "18_18") (pintype "bidirectional"))
    )
    (net (code "175") (name "S01_P") (class "Default")
      (node (ref "X-SOUTH") (pin "16") (pinfunction "16_16") (pintype "bidirectional"))
    )
    (net (code "176") (name "S02_N") (class "Default")
      (node (ref "X-SOUTH") (pin "21") (pinfunction "21_21") (pintype "bidirectional"))
    )
    (net (code "177") (name "S02_P") (class "Default")
      (node (ref "X-SOUTH") (pin "19") (pinfunction "19_19") (pintype "bidirectional"))
    )
    (net (code "178") (name "S03_N") (class "Default")
      (node (ref "X-SOUTH") (pin "24") (pinfunction "24_24") (pintype "bidirectional"))
    )
    (net (code "179") (name "S03_P") (class "Default")
      (node (ref "X-SOUTH") (pin "22") (pinfunction "22_22") (pintype "bidirectional"))
    )
    (net (code "180") (name "S05_N") (class "Default")
      (node (ref "X-SOUTH") (pin "30") (pinfunction "30_30") (pintype "bidirectional"))
    )
    (net (code "181") (name "S05_P") (class "Default")
      (node (ref "X-SOUTH") (pin "28") (pinfunction "28_28") (pintype "bidirectional"))
    )
    (net (code "182") (name "S38_N") (class "Default")
      (node (ref "X-SOUTH") (pin "129") (pinfunction "129_129") (pintype "bidirectional"))
    )
    (net (code "183") (name "S38_P") (class "Default")
      (node (ref "X-SOUTH") (pin "127") (pinfunction "127_127") (pintype "bidirectional"))
    )
    (net (code "184") (name "S39_N") (class "Default")
      (node (ref "X-SOUTH") (pin "132") (pinfunction "132_132") (pintype "bidirectional"))
    )
    (net (code "185") (name "S39_P") (class "Default")
      (node (ref "X-SOUTH") (pin "130") (pinfunction "130_130") (pintype "bidirectional"))
    )
    (net (code "186") (name "SPI_EN") (class "Default")
      (node (ref "X-EAST") (pin "14") (pinfunction "14_14") (pintype "bidirectional"))
      (node (ref "X-NORTH") (pin "120") (pinfunction "120_120") (pintype "bidirectional"))
    )
    (net (code "187") (name "SYS_RES_N") (class "Default")
      (node (ref "X-EAST") (pin "22") (pinfunction "22_22") (pintype "bidirectional"))
      (node (ref "X-NORTH") (pin "126") (pinfunction "126_126") (pintype "bidirectional"))
    )
    (net (code "188") (name "S_CHK_V") (class "Default")
      (node (ref "X-EAST") (pin "92") (pinfunction "92_92") (pintype "bidirectional"))
      (node (ref "X-EAST") (pin "94") (pinfunction "94_94") (pintype "bidirectional"))
      (node (ref "X-SOUTH") (pin "7") (pinfunction "7_7") (pintype "bidirectional"))
      (node (ref "X-SOUTH") (pin "9") (pinfunction "9_9") (pintype "bidirectional"))
    )
    (net (code "189") (name "S_I2C_V") (class "Default")
      (node (ref "X-SOUTH") (pin "136") (pinfunction "136_136") (pintype "bidirectional"))
      (node (ref "X-SOUTH") (pin "138") (pinfunction "138_138") (pintype "bidirectional"))
      (node (ref "X-WEST") (pin "7") (pinfunction "7_7") (pintype "bidirectional"))
      (node (ref "X-WEST") (pin "9") (pinfunction "9_9") (pintype "bidirectional"))
    )
    (net (code "190") (name "S_SCK") (class "Default")
      (node (ref "X-SOUTH") (pin "143") (pinfunction "143_143") (pintype "bidirectional"))
      (node (ref "X-WEST") (pin "2") (pinfunction "2_2") (pintype "bidirectional"))
    )
    (net (code "191") (name "S_SCL") (class "Default")
      (node (ref "X-SOUTH") (pin "144") (pinfunction "144_144") (pintype "bidirectional"))
      (node (ref "X-WEST") (pin "1") (pinfunction "1_1") (pintype "bidirectional"))
    )
    (net (code "192") (name "S_SDA") (class "Default")
      (node (ref "X-SOUTH") (pin "142") (pinfunction "142_142") (pintype "bidirectional"))
      (node (ref "X-WEST") (pin "3") (pinfunction "3_3") (pintype "bidirectional"))
    )
    (net (code "193") (name "S_SDI") (class "Default")
      (node (ref "X-SOUTH") (pin "139") (pinfunction "139_139") (pintype "bidirectional"))
      (node (ref "X-WEST") (pin "6") (pinfunction "6_6") (pintype "bidirectional"))
    )
    (net (code "194") (name "S_SDO") (class "Default")
      (node (ref "X-SOUTH") (pin "141") (pinfunction "141_141") (pintype "bidirectional"))
      (node (ref "X-WEST") (pin "4") (pinfunction "4_4") (pintype "bidirectional"))
    )
    (net (code "195") (name "S_SPI_V") (class "Default")
      (node (ref "X-SOUTH") (pin "133") (pinfunction "133_133") (pintype "bidirectional"))
      (node (ref "X-SOUTH") (pin "135") (pinfunction "135_135") (pintype "bidirectional"))
      (node (ref "X-WEST") (pin "10") (pinfunction "10_10") (pintype "bidirectional"))
      (node (ref "X-WEST") (pin "8") (pinfunction "8_8") (pintype "bidirectional"))
    )
    (net (code "196") (name "S_VE") (class "Default")
      (node (ref "P-E") (pin "5") (pinfunction "5_5") (pintype "passive"))
      (node (ref "X-EAST") (pin "51") (pinfunction "51_51") (pintype "bidirectional"))
      (node (ref "X-EAST") (pin "57") (pinfunction "57_57") (pintype "bidirectional"))
      (node (ref "X-EAST") (pin "63") (pinfunction "63_63") (pintype "bidirectional"))
      (node (ref "X-EAST") (pin "69") (pinfunction "69_69") (pintype "bidirectional"))
      (node (ref "X-SOUTH") (pin "14") (pinfunction "14_14") (pintype "bidirectional"))
      (node (ref "X-SOUTH") (pin "20") (pinfunction "20_20") (pintype "bidirectional"))
      (node (ref "X-SOUTH") (pin "26") (pinfunction "26_26") (pintype "bidirectional"))
      (node (ref "X-SOUTH") (pin "32") (pinfunction "32_32") (pintype "bidirectional"))
      (node (ref "X-SOUTH") (pin "38") (pinfunction "38_38") (pintype "bidirectional"))
    )
    (net (code "197") (name "S_VE_CV") (class "Default")
      (node (ref "X-EAST") (pin "100") (pinfunction "100_100") (pintype "bidirectional"))
      (node (ref "X-SOUTH") (pin "1") (pinfunction "1_1") (pintype "bidirectional"))
    )
    (net (code "198") (name "S_VE_OV") (class "Default")
      (node (ref "X-EAST") (pin "99") (pinfunction "99_99") (pintype "bidirectional"))
      (node (ref "X-SOUTH") (pin "2") (pinfunction "2_2") (pintype "bidirectional"))
    )
    (net (code "199") (name "S_VE_UV") (class "Default")
      (node (ref "X-EAST") (pin "89") (pinfunction "89_89") (pintype "bidirectional"))
      (node (ref "X-SOUTH") (pin "8") (pinfunction "8_8") (pintype "bidirectional"))
    )
    (net (code "200") (name "S_VS") (class "Default")
      (node (ref "P-E") (pin "3") (pinfunction "3_3") (pintype "passive"))
      (node (ref "X-EAST") (pin "32") (pinfunction "32_32") (pintype "bidirectional"))
      (node (ref "X-EAST") (pin "38") (pinfunction "38_38") (pintype "bidirectional"))
      (node (ref "X-EAST") (pin "44") (pinfunction "44_44") (pintype "bidirectional"))
      (node (ref "X-EAST") (pin "50") (pinfunction "50_50") (pintype "bidirectional"))
      (node (ref "X-EAST") (pin "52") (pinfunction "52_52") (pintype "bidirectional"))
      (node (ref "X-EAST") (pin "58") (pinfunction "58_58") (pintype "bidirectional"))
      (node (ref "X-EAST") (pin "64") (pinfunction "64_64") (pintype "bidirectional"))
      (node (ref "X-EAST") (pin "70") (pinfunction "70_70") (pintype "bidirectional"))
      (node (ref "X-SOUTH") (pin "50") (pinfunction "50_50") (pintype "bidirectional"))
      (node (ref "X-SOUTH") (pin "56") (pinfunction "56_56") (pintype "bidirectional"))
      (node (ref "X-SOUTH") (pin "62") (pinfunction "62_62") (pintype "bidirectional"))
      (node (ref "X-SOUTH") (pin "68") (pinfunction "68_68") (pintype "bidirectional"))
      (node (ref "X-SOUTH") (pin "74") (pinfunction "74_74") (pintype "bidirectional"))
      (node (ref "X-SOUTH") (pin "80") (pinfunction "80_80") (pintype "bidirectional"))
      (node (ref "X-SOUTH") (pin "86") (pinfunction "86_86") (pintype "bidirectional"))
      (node (ref "X-SOUTH") (pin "92") (pinfunction "92_92") (pintype "bidirectional"))
      (node (ref "X-SOUTH") (pin "98") (pinfunction "98_98") (pintype "bidirectional"))
    )
    (net (code "201") (name "S_VS_CV") (class "Default")
      (node (ref "X-EAST") (pin "98") (pinfunction "98_98") (pintype "bidirectional"))
      (node (ref "X-SOUTH") (pin "3") (pinfunction "3_3") (pintype "bidirectional"))
    )
    (net (code "202") (name "S_VS_OV") (class "Default")
      (node (ref "X-EAST") (pin "97") (pinfunction "97_97") (pintype "bidirectional"))
      (node (ref "X-SOUTH") (pin "4") (pinfunction "4_4") (pintype "bidirectional"))
    )
    (net (code "203") (name "S_VS_UV") (class "Default")
      (node (ref "X-EAST") (pin "87") (pinfunction "87_87") (pintype "bidirectional"))
      (node (ref "X-SOUTH") (pin "10") (pinfunction "10_10") (pintype "bidirectional"))
    )
    (net (code "204") (name "S_VW") (class "Default")
      (node (ref "P-W") (pin "1") (pinfunction "1_1") (pintype "passive"))
      (node (ref "X-SOUTH") (pin "110") (pinfunction "110_110") (pintype "bidirectional"))
      (node (ref "X-SOUTH") (pin "116") (pinfunction "116_116") (pintype "bidirectional"))
      (node (ref "X-SOUTH") (pin "122") (pinfunction "122_122") (pintype "bidirectional"))
      (node (ref "X-SOUTH") (pin "128") (pinfunction "128_128") (pintype "bidirectional"))
      (node (ref "X-SOUTH") (pin "134") (pinfunction "134_134") (pintype "bidirectional"))
      (node (ref "X-WEST") (pin "31") (pinfunction "31_31") (pintype "bidirectional"))
      (node (ref "X-WEST") (pin "37") (pinfunction "37_37") (pintype "bidirectional"))
      (node (ref "X-WEST") (pin "43") (pinfunction "43_43") (pintype "bidirectional"))
      (node (ref "X-WEST") (pin "49") (pinfunction "49_49") (pintype "bidirectional"))
    )
    (net (code "205") (name "S_VW_CV") (class "Default")
      (node (ref "X-EAST") (pin "96") (pinfunction "96_96") (pintype "bidirectional"))
      (node (ref "X-SOUTH") (pin "5") (pinfunction "5_5") (pintype "bidirectional"))
    )
    (net (code "206") (name "S_VW_OV") (class "Default")
      (node (ref "X-EAST") (pin "95") (pinfunction "95_95") (pintype "bidirectional"))
      (node (ref "X-SOUTH") (pin "6") (pinfunction "6_6") (pintype "bidirectional"))
    )
    (net (code "207") (name "S_VW_UV") (class "Default")
      (node (ref "X-EAST") (pin "85") (pinfunction "85_85") (pintype "bidirectional"))
      (node (ref "X-SOUTH") (pin "12") (pinfunction "12_12") (pintype "bidirectional"))
    )
    (net (code "208") (name "TCK") (class "Default")
      (node (ref "X-WEST") (pin "12") (pinfunction "12_12") (pintype "bidirectional"))
    )
    (net (code "209") (name "TDI") (class "Default")
      (node (ref "X-WEST") (pin "16") (pinfunction "16_16") (pintype "bidirectional"))
    )
    (net (code "210") (name "TDIG1") (class "Default")
      (node (ref "X-EAST") (pin "18") (pinfunction "18_18") (pintype "bidirectional"))
      (node (ref "X-NORTH") (pin "124") (pinfunction "124_124") (pintype "bidirectional"))
    )
    (net (code "211") (name "TDIG2") (class "Default")
      (node (ref "X-EAST") (pin "17") (pinfunction "17_17") (pintype "bidirectional"))
      (node (ref "X-NORTH") (pin "129") (pinfunction "129_129") (pintype "bidirectional"))
    )
    (net (code "212") (name "TDO") (class "Default")
      (node (ref "X-WEST") (pin "18") (pinfunction "18_18") (pintype "bidirectional"))
    )
    (net (code "213") (name "TMS") (class "Default")
      (node (ref "X-WEST") (pin "14") (pinfunction "14_14") (pintype "bidirectional"))
    )
    (net (code "214") (name "T_EXP1") (class "Default")
      (node (ref "X-EAST") (pin "12") (pinfunction "12_12") (pintype "bidirectional"))
      (node (ref "X-NORTH") (pin "132") (pinfunction "132_132") (pintype "bidirectional"))
    )
    (net (code "215") (name "T_EXP2") (class "Default")
      (node (ref "X-EAST") (pin "16") (pinfunction "16_16") (pintype "bidirectional"))
      (node (ref "X-NORTH") (pin "118") (pinfunction "118_118") (pintype "bidirectional"))
    )
    (net (code "216") (name "W_I2C_V") (class "Default")
      (node (ref "X-WEST") (pin "11") (pinfunction "11_11") (pintype "bidirectional"))
      (node (ref "X-WEST") (pin "13") (pinfunction "13_13") (pintype "bidirectional"))
    )
    (net (code "217") (name "W_SCL") (class "Default")
      (node (ref "X-WEST") (pin "15") (pinfunction "15_15") (pintype "bidirectional"))
    )
    (net (code "218") (name "W_SDA") (class "Default")
      (node (ref "X-WEST") (pin "17") (pinfunction "17_17") (pintype "bidirectional"))
    )
    (net (code "219") (name "W_VW") (class "Default")
      (node (ref "X-WEST") (pin "79") (pinfunction "79_79") (pintype "bidirectional"))
      (node (ref "X-WEST") (pin "81") (pinfunction "81_81") (pintype "bidirectional"))
      (node (ref "X-WEST") (pin "83") (pinfunction "83_83") (pintype "bidirectional"))
      (node (ref "X-WEST") (pin "84") (pinfunction "84_84") (pintype "bidirectional"))
      (node (ref "X-WEST") (pin "86") (pinfunction "86_86") (pintype "bidirectional"))
      (node (ref "X-WEST") (pin "88") (pinfunction "88_88") (pintype "bidirectional"))
    )
    (net (code "220") (name "W_VW_CV") (class "Default")
      (node (ref "X-WEST") (pin "90") (pinfunction "90_90") (pintype "bidirectional"))
    )
    (net (code "221") (name "W_VW_OV") (class "Default")
      (node (ref "X-WEST") (pin "93") (pinfunction "93_93") (pintype "bidirectional"))
    )
    (net (code "222") (name "W_VW_UV") (class "Default")
      (node (ref "X-WEST") (pin "91") (pinfunction "91_91") (pintype "bidirectional"))
    )
    (net (code "223") (name "unconnected-(X-EAST-PadM1)") (class "Default")
      (node (ref "X-EAST") (pin "M1") (pinfunction "M1_M1") (pintype "bidirectional"))
    )
    (net (code "224") (name "unconnected-(X-EAST-PadM2)") (class "Default")
      (node (ref "X-EAST") (pin "M2") (pinfunction "M2_M2") (pintype "bidirectional"))
    )
    (net (code "225") (name "unconnected-(X-NORTH-PadM1)") (class "Default")
      (node (ref "X-NORTH") (pin "M1") (pinfunction "M1_M1") (pintype "bidirectional"))
    )
    (net (code "226") (name "unconnected-(X-NORTH-PadM2)") (class "Default")
      (node (ref "X-NORTH") (pin "M2") (pinfunction "M2_M2") (pintype "bidirectional"))
    )
    (net (code "227") (name "unconnected-(X-SOUTH-PadM1)") (class "Default")
      (node (ref "X-SOUTH") (pin "M1") (pinfunction "M1_M1") (pintype "bidirectional"))
    )
    (net (code "228") (name "unconnected-(X-SOUTH-PadM2)") (class "Default")
      (node (ref "X-SOUTH") (pin "M2") (pinfunction "M2_M2") (pintype "bidirectional"))
    )
    (net (code "229") (name "unconnected-(X-WEST-PadM1)") (class "Default")
      (node (ref "X-WEST") (pin "M1") (pinfunction "M1_M1") (pintype "bidirectional"))
    )
    (net (code "230") (name "unconnected-(X-WEST-PadM2)") (class "Default")
      (node (ref "X-WEST") (pin "M2") (pinfunction "M2_M2") (pintype "bidirectional"))
    )
  )
)
